# IO_Filter.net
KiCad netlist of a schematic drawn in Altium Designer
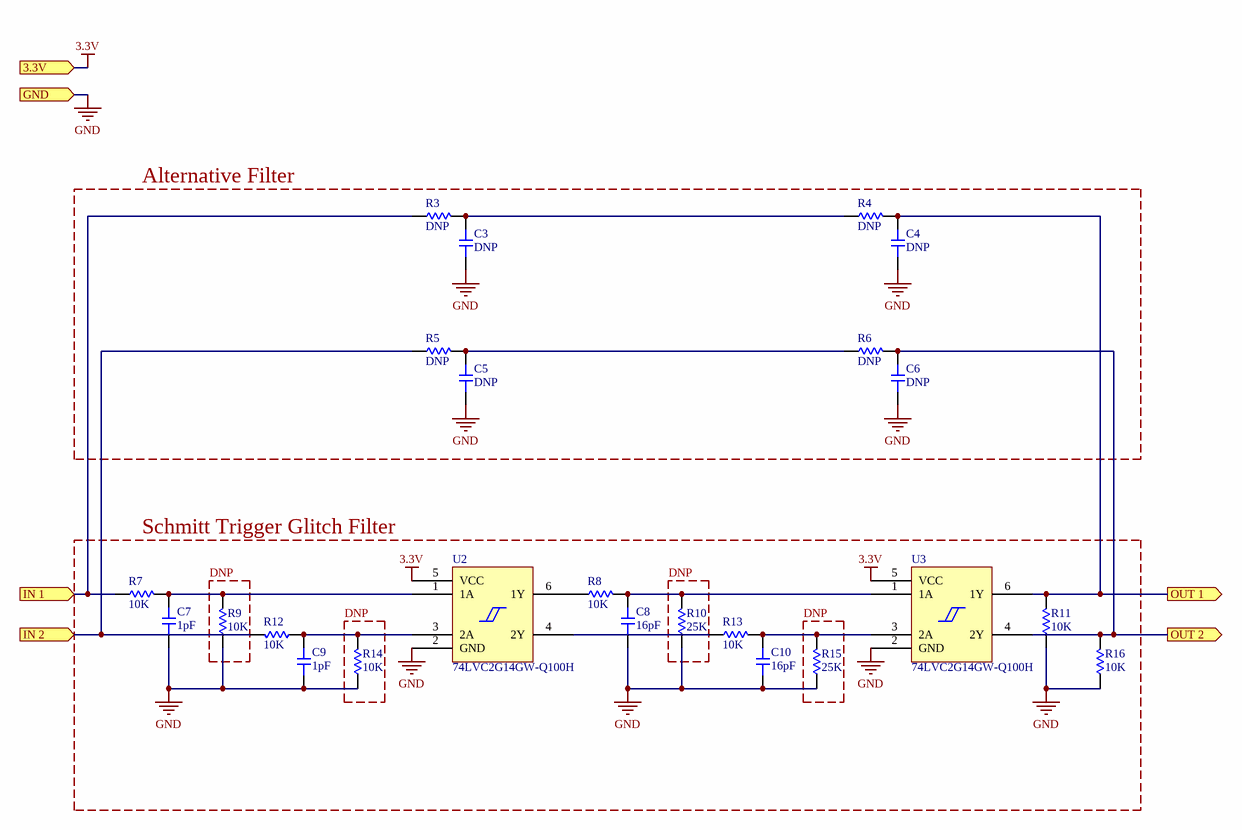
[diagram p0: IO_Filter.SchDoc]

(export (version "E")
  (design (tool "Eeschema 10.0.6"))
  (components
    (comp (ref "C3") (value "DNP") (footprint "0603-CAP") (libsource (lib "IO_Converter") (part "Capacitor")))
    (comp (ref "C4") (value "DNP") (footprint "0603-CAP") (libsource (lib "IO_Converter") (part "Capacitor")))
    (comp (ref "C5") (value "DNP") (footprint "0603-CAP") (libsource (lib "IO_Converter") (part "Capacitor")))
    (comp (ref "C6") (value "DNP") (footprint "0603-CAP") (libsource (lib "IO_Converter") (part "Capacitor")))
    (comp (ref "C7")
      (value "1pF")
      (footprint "0603-CAP")
      (description "±0.1pF 50V Ceramic Capacitor C0G, NP0 0603 (1608 Metric)")
      (fields (field (name "Comment") "CC0603BRNPO9BN1R0"))
      (libsource (lib "IO_Converter") (part "Capacitor 1pF"))
    )
    (comp (ref "C8")
      (value "16pF")
      (footprint "0603-CAP")
      (description "±5% 50V Ceramic Capacitor C0G, NP0 0603 (1608 Metric)")
      (fields (field (name "Comment") "CC0603JRNPO9BN160"))
      (libsource (lib "IO_Converter") (part "Capacitor 16pF"))
    )
    (comp (ref "C9")
      (value "1pF")
      (footprint "0603-CAP")
      (description "±0.1pF 50V Ceramic Capacitor C0G, NP0 0603 (1608 Metric)")
      (fields (field (name "Comment") "CC0603BRNPO9BN1R0"))
      (libsource (lib "IO_Converter") (part "Capacitor 1pF"))
    )
    (comp (ref "C10")
      (value "16pF")
      (footprint "0603-CAP")
      (description "±5% 50V Ceramic Capacitor C0G, NP0 0603 (1608 Metric)")
      (fields (field (name "Comment") "CC0603JRNPO9BN160"))
      (libsource (lib "IO_Converter") (part "Capacitor 16pF"))
    )
    (comp (ref "R3") (value "DNP") (footprint "0603-RES") (libsource (lib "IO_Converter") (part "Resistor")))
    (comp (ref "R4") (value "DNP") (footprint "0603-RES") (libsource (lib "IO_Converter") (part "Resistor")))
    (comp (ref "R5") (value "DNP") (footprint "0603-RES") (libsource (lib "IO_Converter") (part "Resistor")))
    (comp (ref "R6") (value "DNP") (footprint "0603-RES") (libsource (lib "IO_Converter") (part "Resistor")))
    (comp (ref "R7")
      (value "10K")
      (footprint "0603-RES")
      (description "10 ±0.5% 0.1W, 1/10W Chip Resistor 0603 (1608 Metric) - Thin Film")
      (fields (field (name "Comment") "RT0603DRE0710KL"))
      (libsource (lib "IO_Converter") (part "Resisitor 10K"))
    )
    (comp (ref "R8")
      (value "10K")
      (footprint "0603-RES")
      (description "10 ±0.5% 0.1W, 1/10W Chip Resistor 0603 (1608 Metric) - Thin Film")
      (fields (field (name "Comment") "RT0603DRE0710KL"))
      (libsource (lib "IO_Converter") (part "Resisitor 10K"))
    )
    (comp (ref "R9")
      (value "10K")
      (footprint "0603-RES")
      (description "10 ±0.5% 0.1W, 1/10W Chip Resistor 0603 (1608 Metric) - Thin Film")
      (fields (field (name "Comment") "RT0603DRE0710KL"))
      (libsource (lib "IO_Converter") (part "Resisitor 10K"))
    )
    (comp (ref "R10")
      (value "25K")
      (footprint "RESC2012X06N")
      (fields (field (name "Comment") "CPF-A-0805B25KE"))
      (libsource (lib "IO_Converter") (part "Resistor 25K"))
    )
    (comp (ref "R11")
      (value "10K")
      (footprint "0603-RES")
      (description "10 ±0.5% 0.1W, 1/10W Chip Resistor 0603 (1608 Metric) - Thin Film")
      (fields (field (name "Comment") "RT0603DRE0710KL"))
      (libsource (lib "IO_Converter") (part "Resisitor 10K"))
    )
    (comp (ref "R12")
      (value "10K")
      (footprint "0603-RES")
      (description "10 ±0.5% 0.1W, 1/10W Chip Resistor 0603 (1608 Metric) - Thin Film")
      (fields (field (name "Comment") "RT0603DRE0710KL"))
      (libsource (lib "IO_Converter") (part "Resisitor 10K"))
    )
    (comp (ref "R13")
      (value "10K")
      (footprint "0603-RES")
      (description "10 ±0.5% 0.1W, 1/10W Chip Resistor 0603 (1608 Metric) - Thin Film")
      (fields (field (name "Comment") "RT0603DRE0710KL"))
      (libsource (lib "IO_Converter") (part "Resisitor 10K"))
    )
    (comp (ref "R14")
      (value "10K")
      (footprint "0603-RES")
      (description "10 ±0.5% 0.1W, 1/10W Chip Resistor 0603 (1608 Metric) - Thin Film")
      (fields (field (name "Comment") "RT0603DRE0710KL"))
      (libsource (lib "IO_Converter") (part "Resisitor 10K"))
    )
    (comp (ref "R15")
      (value "25K")
      (footprint "RESC2012X06N")
      (fields (field (name "Comment") "CPF-A-0805B25KE"))
      (libsource (lib "IO_Converter") (part "Resistor 25K"))
    )
    (comp (ref "R16")
      (value "10K")
      (footprint "0603-RES")
      (description "10 ±0.5% 0.1W, 1/10W Chip Resistor 0603 (1608 Metric) - Thin Film")
      (fields (field (name "Comment") "RT0603DRE0710KL"))
      (libsource (lib "IO_Converter") (part "Resisitor 10K"))
    )
    (comp (ref "U2")
      (value "74LVC2G14GW-Q100H")
      (footprint "TSOP65P210X110-6N")
      (description "Inverter IC 2 Channel Schmitt Trigger SOT-363")
      (libsource (lib "IO_Converter") (part "74LVC2G14GW-Q100H"))
    )
    (comp (ref "U3")
      (value "74LVC2G14GW-Q100H")
      (footprint "TSOP65P210X110-6N")
      (description "Inverter IC 2 Channel Schmitt Trigger SOT-363")
      (libsource (lib "IO_Converter") (part "74LVC2G14GW-Q100H"))
    )
  )
  (nets
    (net (code "1") (name "/IN 1") (class "Default")
      (node (ref "R3") (pin "1") (pinfunction "1_1") (pintype "passive"))
      (node (ref "R7") (pin "1") (pinfunction "1_1") (pintype "passive"))
    )
    (net (code "2") (name "/IN 2") (class "Default")
      (node (ref "R12") (pin "2") (pinfunction "2_2") (pintype "passive"))
      (node (ref "R5") (pin "1") (pinfunction "1_1") (pintype "passive"))
    )
    (net (code "3") (name "/OUT 1") (class "Default")
      (node (ref "C4") (pin "2") (pinfunction "2_2") (pintype "passive"))
      (node (ref "R11") (pin "2") (pinfunction "2_2") (pintype "passive"))
      (node (ref "R4") (pin "2") (pinfunction "2_2") (pintype "passive"))
      (node (ref "U3") (pin "6") (pinfunction "1Y_6") (pintype "passive"))
    )
    (net (code "4") (name "/OUT 2") (class "Default")
      (node (ref "C6") (pin "2") (pinfunction "2_2") (pintype "passive"))
      (node (ref "R16") (pin "2") (pinfunction "2_2") (pintype "passive"))
      (node (ref "R6") (pin "2") (pinfunction "2_2") (pintype "passive"))
      (node (ref "U3") (pin "4") (pinfunction "2Y_4") (pintype "passive"))
    )
    (net (code "5") (name "3.3V") (class "Default")
      (node (ref "U2") (pin "5") (pinfunction "VCC_5") (pintype "passive"))
      (node (ref "U3") (pin "5") (pinfunction "VCC_5") (pintype "passive"))
    )
    (net (code "6") (name "GND") (class "Default")
      (node (ref "C10") (pin "1") (pinfunction "1_1") (pintype "passive"))
      (node (ref "C3") (pin "1") (pinfunction "1_1") (pintype "passive"))
      (node (ref "C4") (pin "1") (pinfunction "1_1") (pintype "passive"))
      (node (ref "C5") (pin "1") (pinfunction "1_1") (pintype "passive"))
      (node (ref "C6") (pin "1") (pinfunction "1_1") (pintype "passive"))
      (node (ref "C7") (pin "1") (pinfunction "1_1") (pintype "passive"))
      (node (ref "C8") (pin "1") (pinfunction "1_1") (pintype "passive"))
      (node (ref "C9") (pin "1") (pinfunction "1_1") (pintype "passive"))
      (node (ref "R10") (pin "1") (pinfunction "1_1") (pintype "passive"))
      (node (ref "R11") (pin "1") (pinfunction "1_1") (pintype "passive"))
      (node (ref "R14") (pin "1") (pinfunction "1_1") (pintype "passive"))
      (node (ref "R15") (pin "1") (pinfunction "1_1") (pintype "passive"))
      (node (ref "R16") (pin "1") (pinfunction "1_1") (pintype "passive"))
      (node (ref "R9") (pin "1") (pinfunction "1_1") (pintype "passive"))
      (node (ref "U2") (pin "2") (pinfunction "GND_2") (pintype "passive"))
      (node (ref "U3") (pin "2") (pinfunction "GND_2") (pintype "passive"))
    )
    (net (code "7") (name "Net-(C3-Pad2)") (class "Default")
      (node (ref "C3") (pin "2") (pinfunction "2_2") (pintype "passive"))
      (node (ref "R3") (pin "2") (pinfunction "2_2") (pintype "passive"))
      (node (ref "R4") (pin "1") (pinfunction "1_1") (pintype "passive"))
    )
    (net (code "8") (name "Net-(C5-Pad2)") (class "Default")
      (node (ref "C5") (pin "2") (pinfunction "2_2") (pintype "passive"))
      (node (ref "R5") (pin "2") (pinfunction "2_2") (pintype "passive"))
      (node (ref "R6") (pin "1") (pinfunction "1_1") (pintype "passive"))
    )
    (net (code "9") (name "Net-(U2-1A)") (class "Default")
      (node (ref "C7") (pin "2") (pinfunction "2_2") (pintype "passive"))
      (node (ref "R7") (pin "2") (pinfunction "2_2") (pintype "passive"))
      (node (ref "R9") (pin "2") (pinfunction "2_2") (pintype "passive"))
      (node (ref "U2") (pin "1") (pinfunction "1A_1") (pintype "passive"))
    )
    (net (code "10") (name "Net-(U2-1Y)") (class "Default")
      (node (ref "R8") (pin "1") (pinfunction "1_1") (pintype "passive"))
      (node (ref "U2") (pin "6") (pinfunction "1Y_6") (pintype "passive"))
    )
    (net (code "11") (name "Net-(U2-2A)") (class "Default")
      (node (ref "C9") (pin "2") (pinfunction "2_2") (pintype "passive"))
      (node (ref "R12") (pin "1") (pinfunction "1_1") (pintype "passive"))
      (node (ref "R14") (pin "2") (pinfunction "2_2") (pintype "passive"))
      (node (ref "U2") (pin "3") (pinfunction "2A_3") (pintype "passive"))
    )
    (net (code "12") (name "Net-(U2-2Y)") (class "Default")
      (node (ref "R13") (pin "1") (pinfunction "1_1") (pintype "passive"))
      (node (ref "U2") (pin "4") (pinfunction "2Y_4") (pintype "passive"))
    )
    (net (code "13") (name "Net-(U3-1A)") (class "Default")
      (node (ref "C8") (pin "2") (pinfunction "2_2") (pintype "passive"))
      (node (ref "R10") (pin "2") (pinfunction "2_2") (pintype "passive"))
      (node (ref "R8") (pin "2") (pinfunction "2_2") (pintype "passive"))
      (node (ref "U3") (pin "1") (pinfunction "1A_1") (pintype "passive"))
    )
    (net (code "14") (name "Net-(U3-2A)") (class "Default")
      (node (ref "C10") (pin "2") (pinfunction "2_2") (pintype "passive"))
      (node (ref "R13") (pin "2") (pinfunction "2_2") (pintype "passive"))
      (node (ref "R15") (pin "2") (pinfunction "2_2") (pintype "passive"))
      (node (ref "U3") (pin "3") (pinfunction "2A_3") (pintype "passive"))
    )
  )
)
